# 01_Invertor.net
KiCad netlist of a schematic drawn in Altium Designer
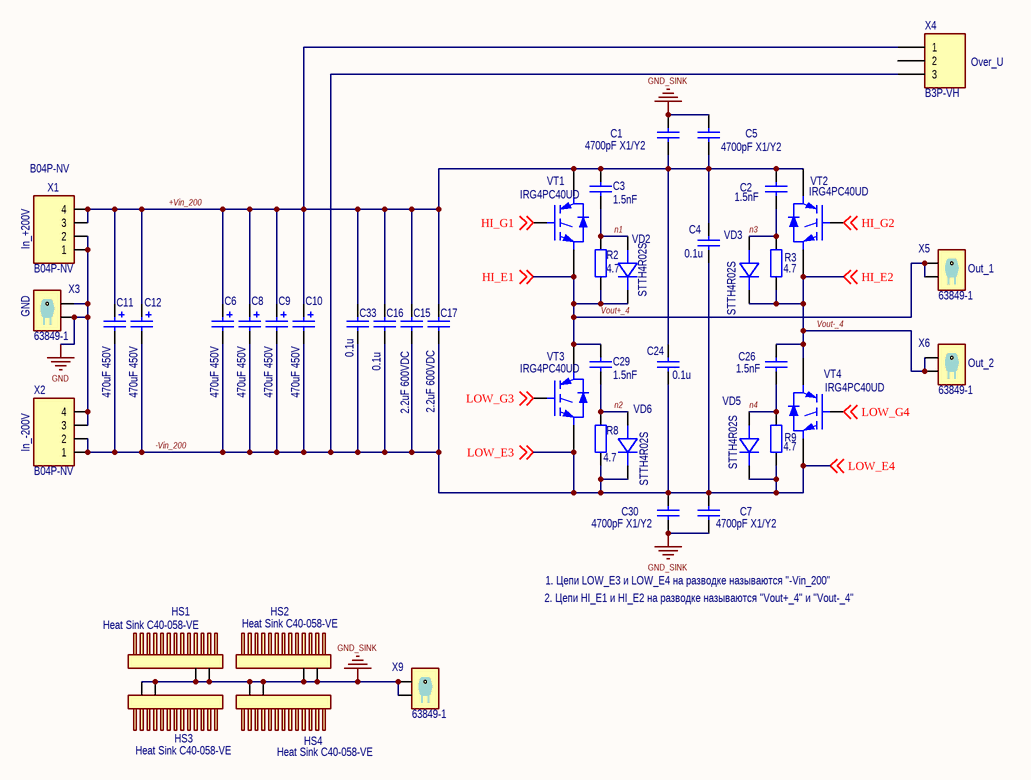
[diagram p0: 01_Invertor.SchDoc]

(export (version "E")
  (design (tool "Eeschema 10.0.6"))
  (components
    (comp (ref "C1")
      (value "4700pF X1/Y2")
      (footprint "mainLib:SMD_C_2220")
      (description "SMD C2220 MURATA 250Vac 10% X7R X1Y2")
      (fields (field (name "PARTNUMBER") "GA355DR7GF472kW01") (field (name "MANUFACTURER") "MURATA"))
      (libsource (lib "mainRCLib") (part "C X1Y2 4700pF SMD 2220 250Vac 10%"))
    )
    (comp (ref "C2")
      (value "1.5nF")
      (footprint "mainLib:SMD_C_1808")
      (description "SMD C 1808 AVX 2kV 10%  X7R")
      (fields (field (name "PARTNUMBER") "1808GC152KAT") (field (name "MANUFACTURER") "AVX"))
      (libsource (lib "mainRCLib") (part "C1808 1.5nF 2KV 10%"))
    )
    (comp (ref "C3")
      (value "1.5nF")
      (footprint "mainLib:SMD_C_1808")
      (description "SMD C 1808 AVX 2kV 10%  X7R")
      (fields (field (name "PARTNUMBER") "1808GC152KAT") (field (name "MANUFACTURER") "AVX"))
      (libsource (lib "mainRCLib") (part "C1808 1.5nF 2KV 10%"))
    )
    (comp (ref "C4")
      (value "0.1u")
      (footprint "mainLib:SMD_C_1812")
      (description "SMD C 1812 MURATA 630V 10% X7R")
      (fields (field (name "PARTNUMBER") "GRM43DR72J104K") (field (name "MANUFACTURER") "MURATA"))
      (libsource (lib "mainRCLib") (part "C1812 0.1u 630V 10%"))
    )
    (comp (ref "C5")
      (value "4700pF X1/Y2")
      (footprint "mainLib:SMD_C_2220")
      (description "SMD C2220 MURATA 250Vac 10% X7R X1Y2")
      (fields (field (name "PARTNUMBER") "GA355DR7GF472kW01") (field (name "MANUFACTURER") "MURATA"))
      (libsource (lib "mainRCLib") (part "C X1Y2 4700pF SMD 2220 250Vac 10%"))
    )
    (comp (ref "C6")
      (value "470uF 450V")
      (footprint "mainLib:El_D35_H45_LS10")
      (description "Aluminum Electrolytic Radial D35 H45 LS10 450V 20%")
      (fields (field (name "PARTNUMBER") "LG450M0470BPF-3545") (field (name "MANUFACTURER") "YAGEO"))
      (libsource (lib "mainRCLib") (part "FC 470uF 20% 450V"))
    )
    (comp (ref "C7")
      (value "4700pF X1/Y2")
      (footprint "mainLib:SMD_C_2220")
      (description "SMD C2220 MURATA 250Vac 10% X7R X1Y2")
      (fields (field (name "PARTNUMBER") "GA355DR7GF472kW01") (field (name "MANUFACTURER") "MURATA"))
      (libsource (lib "mainRCLib") (part "C X1Y2 4700pF SMD 2220 250Vac 10%"))
    )
    (comp (ref "C8")
      (value "470uF 450V")
      (footprint "mainLib:El_D35_H45_LS10")
      (description "Aluminum Electrolytic Radial D35 H45 LS10 450V 20%")
      (fields (field (name "PARTNUMBER") "LG450M0470BPF-3545") (field (name "MANUFACTURER") "YAGEO"))
      (libsource (lib "mainRCLib") (part "FC 470uF 20% 450V"))
    )
    (comp (ref "C9")
      (value "470uF 450V")
      (footprint "mainLib:El_D35_H45_LS10")
      (description "Aluminum Electrolytic Radial D35 H45 LS10 450V 20%")
      (fields (field (name "PARTNUMBER") "LG450M0470BPF-3545") (field (name "MANUFACTURER") "YAGEO"))
      (libsource (lib "mainRCLib") (part "FC 470uF 20% 450V"))
    )
    (comp (ref "C10")
      (value "470uF 450V")
      (footprint "mainLib:El_D35_H45_LS10")
      (description "Aluminum Electrolytic Radial D35 H45 LS10 450V 20%")
      (fields (field (name "PARTNUMBER") "LG450M0470BPF-3545") (field (name "MANUFACTURER") "YAGEO"))
      (libsource (lib "mainRCLib") (part "FC 470uF 20% 450V"))
    )
    (comp (ref "C11")
      (value "470uF 450V")
      (footprint "mainLib:El_D35_H45_LS10")
      (description "Aluminum Electrolytic Radial D35 H45 LS10 450V 20%")
      (fields (field (name "PARTNUMBER") "LG450M0470BPF-3545") (field (name "MANUFACTURER") "YAGEO"))
      (libsource (lib "mainRCLib") (part "FC 470uF 20% 450V"))
    )
    (comp (ref "C12")
      (value "470uF 450V")
      (footprint "mainLib:El_D35_H45_LS10")
      (description "Aluminum Electrolytic Radial D35 H45 LS10 450V 20%")
      (fields (field (name "PARTNUMBER") "LG450M0470BPF-3545") (field (name "MANUFACTURER") "YAGEO"))
      (libsource (lib "mainRCLib") (part "FC 470uF 20% 450V"))
    )
    (comp (ref "C15")
      (value "2.2uF 600VDC")
      (footprint "mainLib:MKP_W20_H39.5_L41.5_LS37.5")
      (description "Polypropelene W20 H39.5 L41.5 LS37.5 600VDC 10%")
      (fields (field (name "PARTNUMBER") "MKP1J042207G00K") (field (name "MANUFACTURER") "Wima"))
      (libsource (lib "mainRCLib") (part "MKP1 2.2uF 10% 600VDC"))
    )
    (comp (ref "C16")
      (value "0.1u")
      (footprint "mainLib:SMD_C_1812")
      (description "SMD C 1812 MURATA 630V 10% X7R")
      (fields (field (name "PARTNUMBER") "GRM43DR72J104K") (field (name "MANUFACTURER") "MURATA"))
      (libsource (lib "mainRCLib") (part "C1812 0.1u 630V 10%"))
    )
    (comp (ref "C17")
      (value "2.2uF 600VDC")
      (footprint "mainLib:MKP_W20_H39.5_L41.5_LS37.5")
      (description "Polypropelene W20 H39.5 L41.5 LS37.5 600VDC 10%")
      (fields (field (name "PARTNUMBER") "MKP1J042207G00K") (field (name "MANUFACTURER") "Wima"))
      (libsource (lib "mainRCLib") (part "MKP1 2.2uF 10% 600VDC"))
    )
    (comp (ref "C24")
      (value "0.1u")
      (footprint "mainLib:SMD_C_1812")
      (description "SMD C 1812 MURATA 630V 10% X7R")
      (fields (field (name "PARTNUMBER") "GRM43DR72J104K") (field (name "MANUFACTURER") "MURATA"))
      (libsource (lib "mainRCLib") (part "C1812 0.1u 630V 10%"))
    )
    (comp (ref "C26")
      (value "1.5nF")
      (footprint "mainLib:SMD_C_1808")
      (description "SMD C 1808 AVX 2kV 10%  X7R")
      (fields (field (name "PARTNUMBER") "1808GC152KAT") (field (name "MANUFACTURER") "AVX"))
      (libsource (lib "mainRCLib") (part "C1808 1.5nF 2KV 10%"))
    )
    (comp (ref "C29")
      (value "1.5nF")
      (footprint "mainLib:SMD_C_1808")
      (description "SMD C 1808 AVX 2kV 10%  X7R")
      (fields (field (name "PARTNUMBER") "1808GC152KAT") (field (name "MANUFACTURER") "AVX"))
      (libsource (lib "mainRCLib") (part "C1808 1.5nF 2KV 10%"))
    )
    (comp (ref "C30")
      (value "4700pF X1/Y2")
      (footprint "mainLib:SMD_C_2220")
      (description "SMD C2220 MURATA 250Vac 10% X7R X1Y2")
      (fields (field (name "PARTNUMBER") "GA355DR7GF472kW01") (field (name "MANUFACTURER") "MURATA"))
      (libsource (lib "mainRCLib") (part "C X1Y2 4700pF SMD 2220 250Vac 10%"))
    )
    (comp (ref "C33")
      (value "0.1u")
      (footprint "mainLib:SMD_C_1812")
      (description "SMD C 1812 MURATA 630V 10% X7R")
      (fields (field (name "PARTNUMBER") "GRM43DR72J104K") (field (name "MANUFACTURER") "MURATA"))
      (libsource (lib "mainRCLib") (part "C1812 0.1u 630V 10%"))
    )
    (comp (ref "HS1")
      (value "Heat Sink C40-058-VE")
      (footprint "mainLib:Heat Sink C40-058-VE")
      (description "Heat Sink")
      (fields (field (name "PARTNUMBER") "C40-058-VE") (field (name "MANUFACTURER") "OLTEST"))
      (libsource (lib "mainLib") (part "Heat Sink C40-058-VE"))
    )
    (comp (ref "HS2")
      (value "Heat Sink C40-058-VE")
      (footprint "mainLib:Heat Sink C40-058-VE")
      (description "Heat Sink")
      (fields (field (name "PARTNUMBER") "C40-058-VE") (field (name "MANUFACTURER") "OLTEST"))
      (libsource (lib "mainLib") (part "Heat Sink C40-058-VE"))
    )
    (comp (ref "HS3")
      (value "Heat Sink C40-058-VE")
      (footprint "mainLib:Heat Sink C40-058-VE")
      (description "Heat Sink")
      (fields (field (name "PARTNUMBER") "C40-058-VE") (field (name "MANUFACTURER") "OLTEST"))
      (libsource (lib "") (part "Heat Sink C40-058-VE_1"))
    )
    (comp (ref "HS4")
      (value "Heat Sink C40-058-VE")
      (footprint "mainLib:Heat Sink C40-058-VE")
      (description "Heat Sink")
      (fields (field (name "PARTNUMBER") "C40-058-VE") (field (name "MANUFACTURER") "OLTEST"))
      (libsource (lib "") (part "Heat Sink C40-058-VE_1"))
    )
    (comp (ref "R2")
      (value "4.7")
      (footprint "mainLib:SMD_R_2512")
      (description "SMD R 2512 VISHAY 1W 500V 1% 100ppm")
      (fields (field (name "PARTNUMBER") "CRCW25124R70FK") (field (name "MANUFACTURER") "VISHAY"))
      (libsource (lib "mainRCLib") (part "R2512 4.7 1%"))
    )
    (comp (ref "R3")
      (value "4.7")
      (footprint "mainLib:SMD_R_2512")
      (description "SMD R 2512 VISHAY 1W 500V 1% 100ppm")
      (fields (field (name "PARTNUMBER") "CRCW25124R70FK") (field (name "MANUFACTURER") "VISHAY"))
      (libsource (lib "mainRCLib") (part "R2512 4.7 1%"))
    )
    (comp (ref "R8")
      (value "4.7")
      (footprint "mainLib:SMD_R_2512")
      (description "SMD R 2512 VISHAY 1W 500V 1% 100ppm")
      (fields (field (name "PARTNUMBER") "CRCW25124R70FK") (field (name "MANUFACTURER") "VISHAY"))
      (libsource (lib "mainRCLib") (part "R2512 4.7 1%"))
    )
    (comp (ref "R9")
      (value "4.7")
      (footprint "mainLib:SMD_R_2512")
      (description "SMD R 2512 VISHAY 1W 500V 1% 100ppm")
      (fields (field (name "PARTNUMBER") "CRCW25124R70FK") (field (name "MANUFACTURER") "VISHAY"))
      (libsource (lib "mainRCLib") (part "R2512 4.7 1%"))
    )
    (comp (ref "VD2")
      (value "STTH4R02S")
      (footprint "mainLib:SMC")
      (description "If=4A, Vf=0.76V Vrrm=200V Diode (SMC)")
      (fields (field (name "MANUFACTURER") "STMicroelectronics"))
      (libsource (lib "mainLib") (part "STTH4R02S"))
    )
    (comp (ref "VD3")
      (value "STTH4R02S")
      (footprint "mainLib:SMC")
      (description "If=4A, Vf=0.76V Vrrm=200V Diode (SMC)")
      (fields (field (name "MANUFACTURER") "STMicroelectronics"))
      (libsource (lib "mainLib") (part "STTH4R02S"))
    )
    (comp (ref "VD5")
      (value "STTH4R02S")
      (footprint "mainLib:SMC")
      (description "If=4A, Vf=0.76V Vrrm=200V Diode (SMC)")
      (fields (field (name "MANUFACTURER") "STMicroelectronics"))
      (libsource (lib "mainLib") (part "STTH4R02S"))
    )
    (comp (ref "VD6")
      (value "STTH4R02S")
      (footprint "mainLib:SMC")
      (description "If=4A, Vf=0.76V Vrrm=200V Diode (SMC)")
      (fields (field (name "MANUFACTURER") "STMicroelectronics"))
      (libsource (lib "mainLib") (part "STTH4R02S"))
    )
    (comp (ref "VT1")
      (value "IRG4PC40UD")
      (footprint "mainLib:TO-247AC-3Pins")
      (description "Insulated Gate Bipolar Transistor with Ultrafast Soft Recovery Diode")
      (fields
        (field (name "MANUFACTURER") "International Rectifier")
        (field (name "PARTNUMBER") "IRG4PC40UDPbF")
      )
      (libsource (lib "mainLib") (part "IRG4PC40UD"))
    )
    (comp (ref "VT2")
      (value "IRG4PC40UD")
      (footprint "mainLib:TO-247AC-3Pins")
      (description "Insulated Gate Bipolar Transistor with Ultrafast Soft Recovery Diode")
      (fields
        (field (name "MANUFACTURER") "International Rectifier")
        (field (name "PARTNUMBER") "IRG4PC40UDPbF")
      )
      (libsource (lib "mainLib") (part "IRG4PC40UD"))
    )
    (comp (ref "VT3")
      (value "IRG4PC40UD")
      (footprint "mainLib:TO-247AC-3Pins")
      (description "Insulated Gate Bipolar Transistor with Ultrafast Soft Recovery Diode")
      (fields
        (field (name "MANUFACTURER") "International Rectifier")
        (field (name "PARTNUMBER") "IRG4PC40UDPbF")
      )
      (libsource (lib "mainLib") (part "IRG4PC40UD"))
    )
    (comp (ref "VT4")
      (value "IRG4PC40UD")
      (footprint "mainLib:TO-247AC-3Pins")
      (description "Insulated Gate Bipolar Transistor with Ultrafast Soft Recovery Diode")
      (fields
        (field (name "MANUFACTURER") "International Rectifier")
        (field (name "PARTNUMBER") "IRG4PC40UDPbF")
      )
      (libsource (lib "mainLib") (part "IRG4PC40UD"))
    )
    (comp (ref "X1")
      (value "B04P-NV")
      (footprint "mainLib:B04P-NV")
      (description "NV 4 конт LS=5.0 10A 250V PCB")
      (fields (field (name "PARTNUMBER") "B04P-NV") (field (name "MANUFACTURER") "JST"))
      (libsource (lib "mainLib") (part "B04P-NV"))
    )
    (comp (ref "X2")
      (value "B04P-NV")
      (footprint "mainLib:B04P-NV")
      (description "NV 4 конт LS=5.0 10A 250V PCB")
      (fields (field (name "MANUFACTURER") "JST"))
      (libsource (lib "mainLib") (part "B04P-NV"))
    )
    (comp (ref "X3")
      (value "63849-1")
      (footprint "mainLib:63849-1+insulator(154719-1)")
      (description "PCB, 6.3х0.8, hole")
      (fields (field (name "MANUFACTURER") "TE Connectivity"))
      (libsource (lib "mainLib") (part "63849-1"))
    )
    (comp (ref "X4")
      (value "B3P-VH")
      (footprint "mainLib:B3P-VH")
      (description "VH Top, 10A 250V 3.96mm")
      (fields (field (name "MANUFACTURER") "JST"))
      (libsource (lib "mainLib") (part "B3P-VH"))
    )
    (comp (ref "X5")
      (value "63849-1")
      (footprint "mainLib:63849-1+insulator(154719-1)")
      (description "PCB, 6.3х0.8, hole")
      (fields (field (name "MANUFACTURER") "TE Connectivity"))
      (libsource (lib "") (part "63849-1_1"))
    )
    (comp (ref "X6")
      (value "63849-1")
      (footprint "mainLib:63849-1+insulator(154719-1)")
      (description "PCB, 6.3х0.8, hole")
      (fields (field (name "MANUFACTURER") "TE Connectivity"))
      (libsource (lib "") (part "63849-1_1"))
    )
    (comp (ref "X9")
      (value "63849-1")
      (footprint "mainLib:63849-1+insulator(154719-1)")
      (description "PCB, 6.3х0.8, hole")
      (fields (field (name "MANUFACTURER") "TE Connectivity"))
      (libsource (lib "") (part "63849-1_1"))
    )
  )
  (nets
    (net (code "1") (name "/+Vin_200") (class "Default")
      (node (ref "C1") (pin "1") (pinfunction "1_1") (pintype "passive"))
      (node (ref "C10") (pin "1") (pinfunction "1_1") (pintype "passive"))
      (node (ref "C11") (pin "1") (pinfunction "1_1") (pintype "passive"))
      (node (ref "C12") (pin "1") (pinfunction "1_1") (pintype "passive"))
      (node (ref "C15") (pin "1") (pinfunction "1_1") (pintype "passive"))
      (node (ref "C16") (pin "2") (pinfunction "2_2") (pintype "passive"))
      (node (ref "C17") (pin "1") (pinfunction "1_1") (pintype "passive"))
      (node (ref "C2") (pin "2") (pinfunction "2_2") (pintype "passive"))
      (node (ref "C24") (pin "2") (pinfunction "2_2") (pintype "passive"))
      (node (ref "C3") (pin "2") (pinfunction "2_2") (pintype "passive"))
      (node (ref "C33") (pin "2") (pinfunction "2_2") (pintype "passive"))
      (node (ref "C4") (pin "2") (pinfunction "2_2") (pintype "passive"))
      (node (ref "C5") (pin "1") (pinfunction "1_1") (pintype "passive"))
      (node (ref "C6") (pin "1") (pinfunction "1_1") (pintype "passive"))
      (node (ref "C8") (pin "1") (pinfunction "1_1") (pintype "passive"))
      (node (ref "C9") (pin "1") (pinfunction "1_1") (pintype "passive"))
      (node (ref "VT1") (pin "2") (pinfunction "C_2") (pintype "passive"))
      (node (ref "VT2") (pin "2") (pinfunction "C_2") (pintype "passive"))
      (node (ref "X1") (pin "3") (pinfunction "3_3") (pintype "passive"))
      (node (ref "X1") (pin "4") (pinfunction "4_4") (pintype "passive"))
      (node (ref "X4") (pin "1") (pinfunction "1_1") (pintype "passive"))
    )
    (net (code "2") (name "/n1") (class "Default")
      (node (ref "C3") (pin "1") (pinfunction "1_1") (pintype "passive"))
      (node (ref "R2") (pin "2") (pinfunction "2_2") (pintype "passive"))
      (node (ref "VD2") (pin "1") (pinfunction "ANODE_1") (pintype "passive"))
    )
    (net (code "3") (name "/n2") (class "Default")
      (node (ref "C29") (pin "1") (pinfunction "1_1") (pintype "passive"))
      (node (ref "R8") (pin "2") (pinfunction "2_2") (pintype "passive"))
      (node (ref "VD6") (pin "1") (pinfunction "ANODE_1") (pintype "passive"))
    )
    (net (code "4") (name "/n3") (class "Default")
      (node (ref "C2") (pin "1") (pinfunction "1_1") (pintype "passive"))
      (node (ref "R3") (pin "2") (pinfunction "2_2") (pintype "passive"))
      (node (ref "VD3") (pin "1") (pinfunction "ANODE_1") (pintype "passive"))
    )
    (net (code "5") (name "/n4") (class "Default")
      (node (ref "C26") (pin "1") (pinfunction "1_1") (pintype "passive"))
      (node (ref "R9") (pin "2") (pinfunction "2_2") (pintype "passive"))
      (node (ref "VD5") (pin "1") (pinfunction "ANODE_1") (pintype "passive"))
    )
    (net (code "6") (name "GND") (class "Default")
      (node (ref "X1") (pin "1") (pinfunction "1_1") (pintype "passive"))
      (node (ref "X1") (pin "2") (pinfunction "2_2") (pintype "passive"))
      (node (ref "X2") (pin "3") (pinfunction "3_3") (pintype "passive"))
      (node (ref "X2") (pin "4") (pinfunction "4_4") (pintype "passive"))
      (node (ref "X3") (pin "1") (pinfunction "1_1") (pintype "passive"))
      (node (ref "X3") (pin "2") (pinfunction "2_2") (pintype "passive"))
    )
    (net (code "7") (name "GND_SINK") (class "Default")
      (node (ref "C1") (pin "2") (pinfunction "2_2") (pintype "passive"))
      (node (ref "C30") (pin "2") (pinfunction "2_2") (pintype "passive"))
      (node (ref "C5") (pin "2") (pinfunction "2_2") (pintype "passive"))
      (node (ref "C7") (pin "1") (pinfunction "1_1") (pintype "passive"))
      (node (ref "HS1") (pin "1") (pinfunction "1_1") (pintype "passive"))
      (node (ref "HS1") (pin "2") (pinfunction "2_2") (pintype "passive"))
      (node (ref "HS2") (pin "1") (pinfunction "1_1") (pintype "passive"))
      (node (ref "HS2") (pin "2") (pinfunction "2_2") (pintype "passive"))
      (node (ref "HS3") (pin "1") (pinfunction "1_1") (pintype "passive"))
      (node (ref "HS3") (pin "2") (pinfunction "2_2") (pintype "passive"))
      (node (ref "HS4") (pin "1") (pinfunction "1_1") (pintype "passive"))
      (node (ref "HS4") (pin "2") (pinfunction "2_2") (pintype "passive"))
      (node (ref "X9") (pin "1") (pinfunction "1_1") (pintype "passive"))
      (node (ref "X9") (pin "2") (pinfunction "2_2") (pintype "passive"))
    )
    (net (code "8") (name "HI_E1") (class "Default")
      (node (ref "C29") (pin "2") (pinfunction "2_2") (pintype "passive"))
      (node (ref "R2") (pin "1") (pinfunction "1_1") (pintype "passive"))
      (node (ref "VD2") (pin "2") (pinfunction "CATHODE_2") (pintype "passive"))
      (node (ref "VT1") (pin "3") (pinfunction "E_3") (pintype "passive"))
      (node (ref "VT3") (pin "2") (pinfunction "C_2") (pintype "passive"))
      (node (ref "X5") (pin "1") (pinfunction "1_1") (pintype "passive"))
      (node (ref "X5") (pin "2") (pinfunction "2_2") (pintype "passive"))
    )
    (net (code "9") (name "HI_E2") (class "Default")
      (node (ref "C26") (pin "2") (pinfunction "2_2") (pintype "passive"))
      (node (ref "R3") (pin "1") (pinfunction "1_1") (pintype "passive"))
      (node (ref "VD3") (pin "2") (pinfunction "CATHODE_2") (pintype "passive"))
      (node (ref "VT2") (pin "3") (pinfunction "E_3") (pintype "passive"))
      (node (ref "VT4") (pin "2") (pinfunction "C_2") (pintype "passive"))
      (node (ref "X6") (pin "1") (pinfunction "1_1") (pintype "passive"))
      (node (ref "X6") (pin "2") (pinfunction "2_2") (pintype "passive"))
    )
    (net (code "10") (name "HI_G1") (class "Default")
      (node (ref "VT1") (pin "1") (pinfunction "G_1") (pintype "passive"))
    )
    (net (code "11") (name "HI_G2") (class "Default")
      (node (ref "VT2") (pin "1") (pinfunction "G_1") (pintype "passive"))
    )
    (net (code "12") (name "LOW_E3") (class "Default")
      (node (ref "C10") (pin "2") (pinfunction "2_2") (pintype "passive"))
      (node (ref "C11") (pin "2") (pinfunction "2_2") (pintype "passive"))
      (node (ref "C12") (pin "2") (pinfunction "2_2") (pintype "passive"))
      (node (ref "C15") (pin "2") (pinfunction "2_2") (pintype "passive"))
      (node (ref "C16") (pin "1") (pinfunction "1_1") (pintype "passive"))
      (node (ref "C17") (pin "2") (pinfunction "2_2") (pintype "passive"))
      (node (ref "C24") (pin "1") (pinfunction "1_1") (pintype "passive"))
      (node (ref "C30") (pin "1") (pinfunction "1_1") (pintype "passive"))
      (node (ref "C33") (pin "1") (pinfunction "1_1") (pintype "passive"))
      (node (ref "C4") (pin "1") (pinfunction "1_1") (pintype "passive"))
      (node (ref "C6") (pin "2") (pinfunction "2_2") (pintype "passive"))
      (node (ref "C7") (pin "2") (pinfunction "2_2") (pintype "passive"))
      (node (ref "C8") (pin "2") (pinfunction "2_2") (pintype "passive"))
      (node (ref "C9") (pin "2") (pinfunction "2_2") (pintype "passive"))
      (node (ref "R8") (pin "1") (pinfunction "1_1") (pintype "passive"))
      (node (ref "R9") (pin "1") (pinfunction "1_1") (pintype "passive"))
      (node (ref "VD5") (pin "2") (pinfunction "CATHODE_2") (pintype "passive"))
      (node (ref "VD6") (pin "2") (pinfunction "CATHODE_2") (pintype "passive"))
      (node (ref "VT3") (pin "3") (pinfunction "E_3") (pintype "passive"))
      (node (ref "VT4") (pin "3") (pinfunction "E_3") (pintype "passive"))
      (node (ref "X2") (pin "1") (pinfunction "1_1") (pintype "passive"))
      (node (ref "X2") (pin "2") (pinfunction "2_2") (pintype "passive"))
      (node (ref "X4") (pin "3") (pinfunction "3_3") (pintype "passive"))
    )
    (net (code "13") (name "LOW_G3") (class "Default")
      (node (ref "VT3") (pin "1") (pinfunction "G_1") (pintype "passive"))
    )
    (net (code "14") (name "LOW_G4") (class "Default")
      (node (ref "VT4") (pin "1") (pinfunction "G_1") (pintype "passive"))
    )
    (net (code "15") (name "unconnected-(X4-Pad2)") (class "Default")
      (node (ref "X4") (pin "2") (pinfunction "2_2") (pintype "passive"))
    )
  )
)
